# Link232-wifi.net
KiCad netlist of a schematic drawn in EAGLE
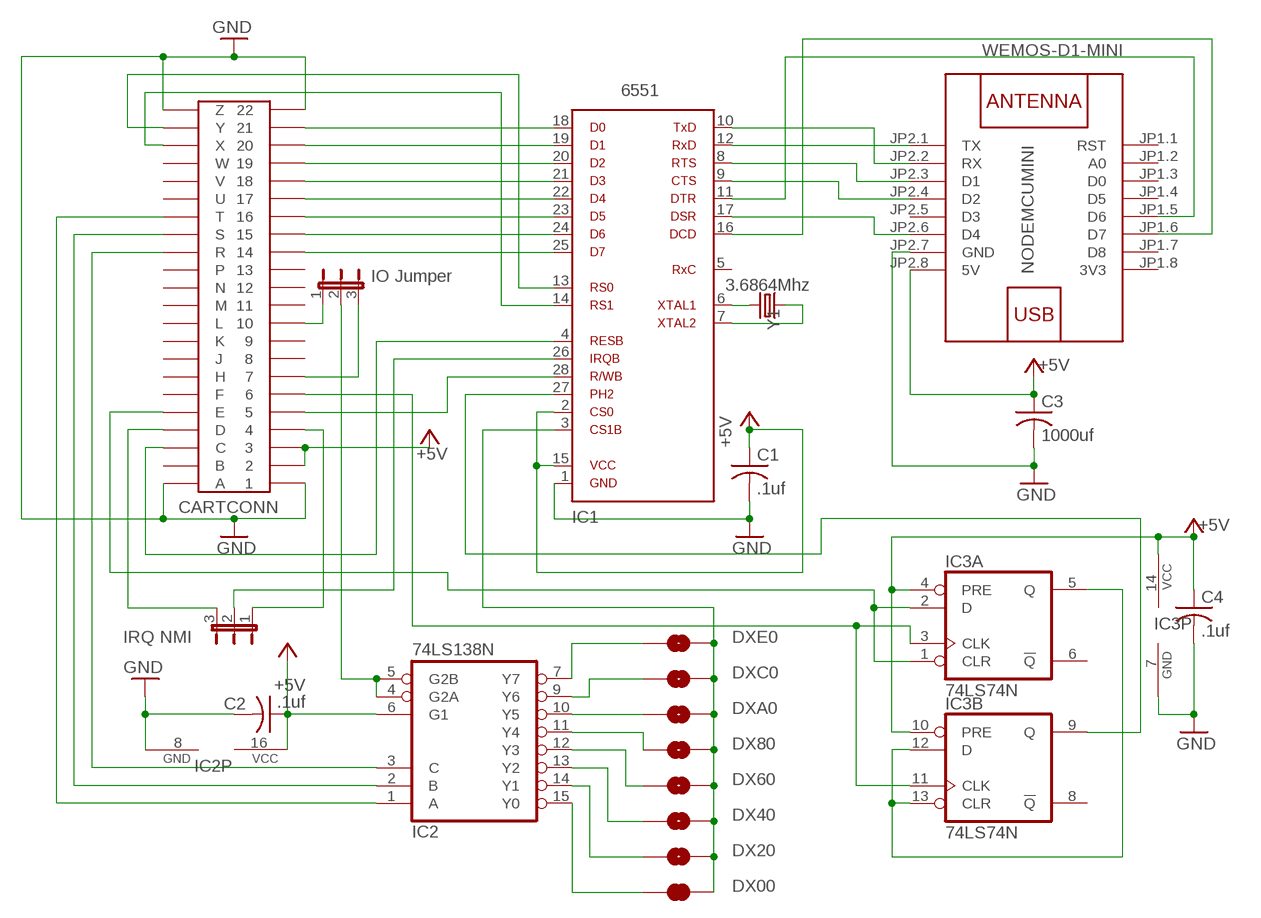
[diagram p0: schematic, sheet 1]

(export (version "E")
  (design (tool "Eeschema 10.0.6"))
  (components
    (comp (ref "C1")
      (value ".1uf")
      (footprint "eagle-import:C050-024X044")
      (libsource (lib "eagle-import") (part "C-US050-024X044"))
    )
    (comp (ref "C2")
      (value ".1uf")
      (footprint "eagle-import:C050-024X044")
      (libsource (lib "eagle-import") (part "C-US050-024X044"))
    )
    (comp (ref "C3")
      (value "1000uf")
      (footprint "eagle-import:C050-024X044")
      (libsource (lib "eagle-import") (part "C-US050-024X044"))
    )
    (comp (ref "C4")
      (value ".1uf")
      (footprint "eagle-import:C050-024X044")
      (libsource (lib "eagle-import") (part "C-US050-024X044"))
    )
    (comp (ref "CARTCONN")
      (value "44PINEDGE")
      (footprint "eagle-import:44PINEDGE")
      (libsource (lib "eagle-import") (part "44PINEDGE"))
    )
    (comp (ref "DF/DE")
      (value "IO Jumper")
      (footprint "eagle-import:JP2")
      (libsource (lib "eagle-import") (part "JP2E"))
    )
    (comp (ref "DX00")
      (value "JUMPER-SMT_2_NC_TRACE_SILK")
      (footprint "eagle-import:SMT-JUMPER_2_NC_TRACE_SILK")
      (libsource (lib "eagle-import") (part "JUMPER-SMT_2_NC_TRACE_SILK"))
    )
    (comp (ref "DX20")
      (value "JUMPER-SMT_2_NO_SILK")
      (footprint "eagle-import:SMT-JUMPER_2_NO_SILK")
      (libsource (lib "eagle-import") (part "JUMPER-SMT_2_NO_SILK"))
    )
    (comp (ref "DX40")
      (value "JUMPER-SMT_2_NO_SILK")
      (footprint "eagle-import:SMT-JUMPER_2_NO_SILK")
      (libsource (lib "eagle-import") (part "JUMPER-SMT_2_NO_SILK"))
    )
    (comp (ref "DX60")
      (value "JUMPER-SMT_2_NO_SILK")
      (footprint "eagle-import:SMT-JUMPER_2_NO_SILK")
      (libsource (lib "eagle-import") (part "JUMPER-SMT_2_NO_SILK"))
    )
    (comp (ref "DX80")
      (value "JUMPER-SMT_2_NO_SILK")
      (footprint "eagle-import:SMT-JUMPER_2_NO_SILK")
      (libsource (lib "eagle-import") (part "JUMPER-SMT_2_NO_SILK"))
    )
    (comp (ref "DXA0")
      (value "JUMPER-SMT_2_NO_SILK")
      (footprint "eagle-import:SMT-JUMPER_2_NO_SILK")
      (libsource (lib "eagle-import") (part "JUMPER-SMT_2_NO_SILK"))
    )
    (comp (ref "DXC0")
      (value "JUMPER-SMT_2_NO_SILK")
      (footprint "eagle-import:SMT-JUMPER_2_NO_SILK")
      (libsource (lib "eagle-import") (part "JUMPER-SMT_2_NO_SILK"))
    )
    (comp (ref "DXE0")
      (value "JUMPER-SMT_2_NO_SILK")
      (footprint "eagle-import:SMT-JUMPER_2_NO_SILK")
      (libsource (lib "eagle-import") (part "JUMPER-SMT_2_NO_SILK"))
    )
    (comp (ref "IC1")
      (value "6551A")
      (footprint "eagle-import:6551")
      (libsource (lib "eagle-import") (part "6551"))
    )
    (comp (ref "IC2")
      (value "74LS138N")
      (footprint "eagle-import:DIL16")
      (libsource (lib "eagle-import") (part "74138NLS"))
    )
    (comp (ref "IC3")
      (value "74LS74N")
      (footprint "eagle-import:DIL14")
      (libsource (lib "eagle-import") (part "7474NLS"))
    )
    (comp (ref "IRQ/NMI")
      (value "IRQ NMI")
      (footprint "eagle-import:JP2")
      (libsource (lib "eagle-import") (part "JP2E"))
    )
    (comp (ref "NODEMCUMINI")
      (value "WEMOS-D1-MINI")
      (footprint "eagle-import:WEMOS-D1-MINI")
      (libsource (lib "eagle-import") (part "WEMOS-D1-MINI"))
    )
    (comp (ref "Y1")
      (value "3.6864Mhz")
      (footprint "eagle-import:HC49US")
      (libsource (lib "eagle-import") (part "CRYSTALPTH-HC49US"))
    )
  )
  (nets
    (net (code "1") (name "+5V") (class "Default")
      (node (ref "C1") (pin "1") (pinfunction "1_1") (pintype "passive"))
      (node (ref "C2") (pin "1") (pinfunction "1_1") (pintype "passive"))
      (node (ref "C3") (pin "1") (pinfunction "1_1") (pintype "passive"))
      (node (ref "C4") (pin "1") (pinfunction "1_1") (pintype "passive"))
      (node (ref "CARTCONN") (pin "2") (pinfunction "2_2") (pintype "passive"))
      (node (ref "CARTCONN") (pin "3") (pinfunction "3_3") (pintype "passive"))
      (node (ref "IC1") (pin "15") (pinfunction "15_15") (pintype "passive"))
      (node (ref "IC1") (pin "2") (pinfunction "2_2") (pintype "passive"))
      (node (ref "IC2") (pin "16") (pinfunction "VCC_16") (pintype "power_in"))
      (node (ref "IC2") (pin "6") (pinfunction "G1_6") (pintype "input"))
      (node (ref "IC3") (pin "10") (pinfunction "PRE_10") (pintype "input"))
      (node (ref "IC3") (pin "14") (pinfunction "VCC_14") (pintype "power_in"))
      (node (ref "IC3") (pin "4") (pinfunction "PRE_4") (pintype "input"))
      (node (ref "NODEMCUMINI") (pin "JP2.8") (pinfunction "5V_JP2.8") (pintype "power_in"))
    )
    (net (code "2") (name "/3V3") (class "Default")
      (node (ref "NODEMCUMINI") (pin "JP1.8") (pinfunction "3V3_JP1.8") (pintype "power_in"))
    )
    (net (code "3") (name "GND") (class "Default")
      (node (ref "C1") (pin "2") (pinfunction "2_2") (pintype "passive"))
      (node (ref "C2") (pin "2") (pinfunction "2_2") (pintype "passive"))
      (node (ref "C3") (pin "2") (pinfunction "2_2") (pintype "passive"))
      (node (ref "C4") (pin "2") (pinfunction "2_2") (pintype "passive"))
      (node (ref "CARTCONN") (pin "1") (pinfunction "1_1") (pintype "passive"))
      (node (ref "CARTCONN") (pin "22") (pinfunction "22_22") (pintype "passive"))
      (node (ref "CARTCONN") (pin "A") (pinfunction "A_A") (pintype "passive"))
      (node (ref "CARTCONN") (pin "Z") (pinfunction "Z_Z") (pintype "passive"))
      (node (ref "IC1") (pin "1") (pinfunction "1_1") (pintype "passive"))
      (node (ref "IC2") (pin "8") (pinfunction "GND_8") (pintype "power_in"))
      (node (ref "IC3") (pin "7") (pinfunction "GND_7") (pintype "power_in"))
      (node (ref "NODEMCUMINI") (pin "JP2.7") (pinfunction "GND_JP2.7") (pintype "power_in"))
    )
    (net (code "4") (name "Net-(CARTCONN-Pad4)") (class "Default")
      (node (ref "CARTCONN") (pin "4") (pinfunction "4_4") (pintype "passive"))
      (node (ref "IRQ/NMI") (pin "1") (pinfunction "1_1") (pintype "passive"))
    )
    (net (code "5") (name "Net-(CARTCONN-Pad5)") (class "Default")
      (node (ref "CARTCONN") (pin "5") (pinfunction "5_5") (pintype "passive"))
      (node (ref "IC1") (pin "28") (pinfunction "28_28") (pintype "passive"))
    )
    (net (code "6") (name "Net-(CARTCONN-Pad7)") (class "Default")
      (node (ref "CARTCONN") (pin "7") (pinfunction "7_7") (pintype "passive"))
      (node (ref "DF/DE") (pin "3") (pinfunction "3_3") (pintype "passive"))
    )
    (net (code "7") (name "Net-(CARTCONN-Pad10)") (class "Default")
      (node (ref "CARTCONN") (pin "10") (pinfunction "10_10") (pintype "passive"))
      (node (ref "DF/DE") (pin "1") (pinfunction "1_1") (pintype "passive"))
    )
    (net (code "8") (name "Net-(CARTCONN-Pad14)") (class "Default")
      (node (ref "CARTCONN") (pin "14") (pinfunction "14_14") (pintype "passive"))
      (node (ref "IC1") (pin "25") (pinfunction "25_25") (pintype "passive"))
    )
    (net (code "9") (name "Net-(CARTCONN-Pad15)") (class "Default")
      (node (ref "CARTCONN") (pin "15") (pinfunction "15_15") (pintype "passive"))
      (node (ref "IC1") (pin "24") (pinfunction "24_24") (pintype "passive"))
    )
    (net (code "10") (name "Net-(CARTCONN-Pad16)") (class "Default")
      (node (ref "CARTCONN") (pin "16") (pinfunction "16_16") (pintype "passive"))
      (node (ref "IC1") (pin "23") (pinfunction "23_23") (pintype "passive"))
    )
    (net (code "11") (name "Net-(CARTCONN-Pad17)") (class "Default")
      (node (ref "CARTCONN") (pin "17") (pinfunction "17_17") (pintype "passive"))
      (node (ref "IC1") (pin "22") (pinfunction "22_22") (pintype "passive"))
    )
    (net (code "12") (name "Net-(CARTCONN-Pad18)") (class "Default")
      (node (ref "CARTCONN") (pin "18") (pinfunction "18_18") (pintype "passive"))
      (node (ref "IC1") (pin "21") (pinfunction "21_21") (pintype "passive"))
    )
    (net (code "13") (name "Net-(CARTCONN-Pad19)") (class "Default")
      (node (ref "CARTCONN") (pin "19") (pinfunction "19_19") (pintype "passive"))
      (node (ref "IC1") (pin "20") (pinfunction "20_20") (pintype "passive"))
    )
    (net (code "14") (name "Net-(CARTCONN-Pad20)") (class "Default")
      (node (ref "CARTCONN") (pin "20") (pinfunction "20_20") (pintype "passive"))
      (node (ref "IC1") (pin "19") (pinfunction "19_19") (pintype "passive"))
    )
    (net (code "15") (name "Net-(CARTCONN-Pad21)") (class "Default")
      (node (ref "CARTCONN") (pin "21") (pinfunction "21_21") (pintype "passive"))
      (node (ref "IC1") (pin "18") (pinfunction "18_18") (pintype "passive"))
    )
    (net (code "16") (name "Net-(CARTCONN-PadC)") (class "Default")
      (node (ref "CARTCONN") (pin "C") (pinfunction "C_C") (pintype "passive"))
      (node (ref "IC1") (pin "4") (pinfunction "4_4") (pintype "passive"))
    )
    (net (code "17") (name "Net-(CARTCONN-PadD)") (class "Default")
      (node (ref "CARTCONN") (pin "D") (pinfunction "D_D") (pintype "passive"))
      (node (ref "IRQ/NMI") (pin "3") (pinfunction "3_3") (pintype "passive"))
    )
    (net (code "18") (name "Net-(CARTCONN-PadX)") (class "Default")
      (node (ref "CARTCONN") (pin "X") (pinfunction "X_X") (pintype "passive"))
      (node (ref "IC1") (pin "14") (pinfunction "14_14") (pintype "passive"))
    )
    (net (code "19") (name "Net-(CARTCONN-PadY)") (class "Default")
      (node (ref "CARTCONN") (pin "Y") (pinfunction "Y_Y") (pintype "passive"))
      (node (ref "IC1") (pin "13") (pinfunction "13_13") (pintype "passive"))
    )
    (net (code "20") (name "Net-(DX00-Pad2)") (class "Default")
      (node (ref "DX00") (pin "2") (pinfunction "2_2") (pintype "passive"))
      (node (ref "DX20") (pin "2") (pinfunction "2_2") (pintype "passive"))
      (node (ref "DX40") (pin "2") (pinfunction "2_2") (pintype "passive"))
      (node (ref "DX60") (pin "2") (pinfunction "2_2") (pintype "passive"))
      (node (ref "DX80") (pin "2") (pinfunction "2_2") (pintype "passive"))
      (node (ref "DXA0") (pin "2") (pinfunction "2_2") (pintype "passive"))
      (node (ref "DXC0") (pin "2") (pinfunction "2_2") (pintype "passive"))
      (node (ref "DXE0") (pin "2") (pinfunction "2_2") (pintype "passive"))
      (node (ref "IC1") (pin "3") (pinfunction "3_3") (pintype "passive"))
    )
    (net (code "21") (name "Net-(IC1-Pad6)") (class "Default")
      (node (ref "IC1") (pin "6") (pinfunction "6_6") (pintype "passive"))
      (node (ref "Y1") (pin "2") (pinfunction "2_2") (pintype "passive"))
    )
    (net (code "22") (name "Net-(IC1-Pad7)") (class "Default")
      (node (ref "IC1") (pin "7") (pinfunction "7_7") (pintype "passive"))
      (node (ref "Y1") (pin "1") (pinfunction "1_1") (pintype "passive"))
    )
    (net (code "23") (name "Net-(IC1-Pad26)") (class "Default")
      (node (ref "IC1") (pin "26") (pinfunction "26_26") (pintype "passive"))
      (node (ref "IRQ/NMI") (pin "2") (pinfunction "2_2") (pintype "passive"))
    )
    (net (code "24") (name "Net-(IC2A-A)") (class "Default")
      (node (ref "CARTCONN") (pin "T") (pinfunction "T_T") (pintype "passive"))
      (node (ref "IC2") (pin "1") (pinfunction "A_1") (pintype "input"))
    )
    (net (code "25") (name "Net-(IC2A-B)") (class "Default")
      (node (ref "CARTCONN") (pin "S") (pinfunction "S_S") (pintype "passive"))
      (node (ref "IC2") (pin "2") (pinfunction "B_2") (pintype "input"))
    )
    (net (code "26") (name "Net-(IC2A-C)") (class "Default")
      (node (ref "CARTCONN") (pin "R") (pinfunction "R_R") (pintype "passive"))
      (node (ref "IC2") (pin "3") (pinfunction "C_3") (pintype "input"))
    )
    (net (code "27") (name "Net-(IC2A-G2A)") (class "Default")
      (node (ref "DF/DE") (pin "2") (pinfunction "2_2") (pintype "passive"))
      (node (ref "IC2") (pin "4") (pinfunction "G2A_4") (pintype "input"))
      (node (ref "IC2") (pin "5") (pinfunction "G2B_5") (pintype "input"))
    )
    (net (code "28") (name "Net-(IC2A-Y0)") (class "Default")
      (node (ref "DX00") (pin "1") (pinfunction "1_1") (pintype "passive"))
      (node (ref "IC2") (pin "15") (pinfunction "Y0_15") (pintype "output"))
    )
    (net (code "29") (name "Net-(IC2A-Y1)") (class "Default")
      (node (ref "DX20") (pin "1") (pinfunction "1_1") (pintype "passive"))
      (node (ref "IC2") (pin "14") (pinfunction "Y1_14") (pintype "output"))
    )
    (net (code "30") (name "Net-(IC2A-Y2)") (class "Default")
      (node (ref "DX40") (pin "1") (pinfunction "1_1") (pintype "passive"))
      (node (ref "IC2") (pin "13") (pinfunction "Y2_13") (pintype "output"))
    )
    (net (code "31") (name "Net-(IC2A-Y3)") (class "Default")
      (node (ref "DX60") (pin "1") (pinfunction "1_1") (pintype "passive"))
      (node (ref "IC2") (pin "12") (pinfunction "Y3_12") (pintype "output"))
    )
    (net (code "32") (name "Net-(IC2A-Y4)") (class "Default")
      (node (ref "DX80") (pin "1") (pinfunction "1_1") (pintype "passive"))
      (node (ref "IC2") (pin "11") (pinfunction "Y4_11") (pintype "output"))
    )
    (net (code "33") (name "Net-(IC2A-Y5)") (class "Default")
      (node (ref "DXA0") (pin "1") (pinfunction "1_1") (pintype "passive"))
      (node (ref "IC2") (pin "10") (pinfunction "Y5_10") (pintype "output"))
    )
    (net (code "34") (name "Net-(IC2A-Y6)") (class "Default")
      (node (ref "DXC0") (pin "1") (pinfunction "1_1") (pintype "passive"))
      (node (ref "IC2") (pin "9") (pinfunction "Y6_9") (pintype "output"))
    )
    (net (code "35") (name "Net-(IC2A-Y7)") (class "Default")
      (node (ref "DXE0") (pin "1") (pinfunction "1_1") (pintype "passive"))
      (node (ref "IC2") (pin "7") (pinfunction "Y7_7") (pintype "output"))
    )
    (net (code "36") (name "Net-(IC3A-CLK)") (class "Default")
      (node (ref "CARTCONN") (pin "6") (pinfunction "6_6") (pintype "passive"))
      (node (ref "IC3") (pin "11") (pinfunction "CLK_11") (pintype "input"))
      (node (ref "IC3") (pin "3") (pinfunction "CLK_3") (pintype "input"))
    )
    (net (code "37") (name "Net-(IC3A-CLR)") (class "Default")
      (node (ref "CARTCONN") (pin "E") (pinfunction "E_E") (pintype "passive"))
      (node (ref "IC3") (pin "1") (pinfunction "CLR_1") (pintype "input"))
      (node (ref "IC3") (pin "2") (pinfunction "D_2") (pintype "input"))
    )
    (net (code "38") (name "Net-(IC3A-Q)") (class "Default")
      (node (ref "IC3") (pin "12") (pinfunction "D_12") (pintype "input"))
      (node (ref "IC3") (pin "13") (pinfunction "CLR_13") (pintype "input"))
      (node (ref "IC3") (pin "5") (pinfunction "Q_5") (pintype "output"))
    )
    (net (code "39") (name "Net-(IC3B-Q)") (class "Default")
      (node (ref "IC1") (pin "27") (pinfunction "27_27") (pintype "passive"))
      (node (ref "IC3") (pin "9") (pinfunction "Q_9") (pintype "output"))
    )
    (net (code "40") (name "Net-(NODEMCUMINI-D1)") (class "Default")
      (node (ref "IC1") (pin "8") (pinfunction "8_8") (pintype "passive"))
      (node (ref "NODEMCUMINI") (pin "JP2.3") (pinfunction "D1_JP2.3") (pintype "bidirectional"))
    )
    (net (code "41") (name "Net-(NODEMCUMINI-D2)") (class "Default")
      (node (ref "IC1") (pin "9") (pinfunction "9_9") (pintype "passive"))
      (node (ref "NODEMCUMINI") (pin "JP2.4") (pinfunction "D2_JP2.4") (pintype "bidirectional"))
    )
    (net (code "42") (name "Net-(NODEMCUMINI-D4)") (class "Default")
      (node (ref "IC1") (pin "17") (pinfunction "17_17") (pintype "passive"))
      (node (ref "NODEMCUMINI") (pin "JP2.6") (pinfunction "D4_JP2.6") (pintype "bidirectional"))
    )
    (net (code "43") (name "Net-(NODEMCUMINI-D6)") (class "Default")
      (node (ref "IC1") (pin "11") (pinfunction "11_11") (pintype "passive"))
      (node (ref "NODEMCUMINI") (pin "JP1.5") (pinfunction "D6_JP1.5") (pintype "bidirectional"))
    )
    (net (code "44") (name "Net-(NODEMCUMINI-D7)") (class "Default")
      (node (ref "IC1") (pin "16") (pinfunction "16_16") (pintype "passive"))
      (node (ref "NODEMCUMINI") (pin "JP1.6") (pinfunction "D7_JP1.6") (pintype "bidirectional"))
    )
    (net (code "45") (name "Net-(NODEMCUMINI-RX)") (class "Default")
      (node (ref "IC1") (pin "10") (pinfunction "10_10") (pintype "passive"))
      (node (ref "NODEMCUMINI") (pin "JP2.2") (pinfunction "RX_JP2.2") (pintype "bidirectional"))
    )
    (net (code "46") (name "Net-(NODEMCUMINI-TX)") (class "Default")
      (node (ref "IC1") (pin "12") (pinfunction "12_12") (pintype "passive"))
      (node (ref "NODEMCUMINI") (pin "JP2.1") (pinfunction "TX_JP2.1") (pintype "bidirectional"))
    )
    (net (code "47") (name "unconnected-(CARTCONN-Pad8)") (class "Default")
      (node (ref "CARTCONN") (pin "8") (pinfunction "8_8") (pintype "passive"))
    )
    (net (code "48") (name "unconnected-(CARTCONN-Pad9)") (class "Default")
      (node (ref "CARTCONN") (pin "9") (pinfunction "9_9") (pintype "passive"))
    )
    (net (code "49") (name "unconnected-(CARTCONN-Pad11)") (class "Default")
      (node (ref "CARTCONN") (pin "11") (pinfunction "11_11") (pintype "passive"))
    )
    (net (code "50") (name "unconnected-(CARTCONN-Pad12)") (class "Default")
      (node (ref "CARTCONN") (pin "12") (pinfunction "12_12") (pintype "passive"))
    )
    (net (code "51") (name "unconnected-(CARTCONN-Pad13)") (class "Default")
      (node (ref "CARTCONN") (pin "13") (pinfunction "13_13") (pintype "passive"))
    )
    (net (code "52") (name "unconnected-(CARTCONN-PadB)") (class "Default")
      (node (ref "CARTCONN") (pin "B") (pinfunction "B_B") (pintype "passive"))
    )
    (net (code "53") (name "unconnected-(CARTCONN-PadF)") (class "Default")
      (node (ref "CARTCONN") (pin "F") (pinfunction "F_F") (pintype "passive"))
    )
    (net (code "54") (name "unconnected-(CARTCONN-PadH)") (class "Default")
      (node (ref "CARTCONN") (pin "H") (pinfunction "H_H") (pintype "passive"))
    )
    (net (code "55") (name "unconnected-(CARTCONN-PadJ)") (class "Default")
      (node (ref "CARTCONN") (pin "J") (pinfunction "J_J") (pintype "passive"))
    )
    (net (code "56") (name "unconnected-(CARTCONN-PadK)") (class "Default")
      (node (ref "CARTCONN") (pin "K") (pinfunction "K_K") (pintype "passive"))
    )
    (net (code "57") (name "unconnected-(CARTCONN-PadL)") (class "Default")
      (node (ref "CARTCONN") (pin "L") (pinfunction "L_L") (pintype "passive"))
    )
    (net (code "58") (name "unconnected-(CARTCONN-PadM)") (class "Default")
      (node (ref "CARTCONN") (pin "M") (pinfunction "M_M") (pintype "passive"))
    )
    (net (code "59") (name "unconnected-(CARTCONN-PadN)") (class "Default")
      (node (ref "CARTCONN") (pin "N") (pinfunction "N_N") (pintype "passive"))
    )
    (net (code "60") (name "unconnected-(CARTCONN-PadP)") (class "Default")
      (node (ref "CARTCONN") (pin "P") (pinfunction "P_P") (pintype "passive"))
    )
    (net (code "61") (name "unconnected-(CARTCONN-PadU)") (class "Default")
      (node (ref "CARTCONN") (pin "U") (pinfunction "U_U") (pintype "passive"))
    )
    (net (code "62") (name "unconnected-(CARTCONN-PadV)") (class "Default")
      (node (ref "CARTCONN") (pin "V") (pinfunction "V_V") (pintype "passive"))
    )
    (net (code "63") (name "unconnected-(CARTCONN-PadW)") (class "Default")
      (node (ref "CARTCONN") (pin "W") (pinfunction "W_W") (pintype "passive"))
    )
    (net (code "64") (name "unconnected-(IC1-Pad5)") (class "Default")
      (node (ref "IC1") (pin "5") (pinfunction "5_5") (pintype "passive"))
    )
    (net (code "65") (name "unconnected-(IC3A-~{Q}-Pad6)") (class "Default")
      (node (ref "IC3") (pin "6") (pinfunction "~{Q}_6") (pintype "output"))
    )
    (net (code "66") (name "unconnected-(IC3B-~{Q}-Pad8)") (class "Default")
      (node (ref "IC3") (pin "8") (pinfunction "~{Q}_8") (pintype "output"))
    )
    (net (code "67") (name "unconnected-(NODEMCUMINI-A0-PadJP1.2)") (class "Default")
      (node (ref "NODEMCUMINI") (pin "JP1.2") (pinfunction "A0_JP1.2") (pintype "bidirectional"))
    )
    (net (code "68") (name "unconnected-(NODEMCUMINI-D0-PadJP1.3)") (class "Default")
      (node (ref "NODEMCUMINI") (pin "JP1.3") (pinfunction "D0_JP1.3") (pintype "bidirectional"))
    )
    (net (code "69") (name "unconnected-(NODEMCUMINI-D3-PadJP2.5)") (class "Default")
      (node (ref "NODEMCUMINI") (pin "JP2.5") (pinfunction "D3_JP2.5") (pintype "bidirectional"))
    )
    (net (code "70") (name "unconnected-(NODEMCUMINI-D5-PadJP1.4)") (class "Default")
      (node (ref "NODEMCUMINI") (pin "JP1.4") (pinfunction "D5_JP1.4") (pintype "bidirectional"))
    )
    (net (code "71") (name "unconnected-(NODEMCUMINI-D8-PadJP1.7)") (class "Default")
      (node (ref "NODEMCUMINI") (pin "JP1.7") (pinfunction "D8_JP1.7") (pintype "bidirectional"))
    )
    (net (code "72") (name "unconnected-(NODEMCUMINI-RST-PadJP1.1)") (class "Default")
      (node (ref "NODEMCUMINI") (pin "JP1.1") (pinfunction "RST_JP1.1") (pintype "bidirectional"))
    )
  )
)
